# TM1628.net
KiCad netlist of a schematic drawn in Altium Designer
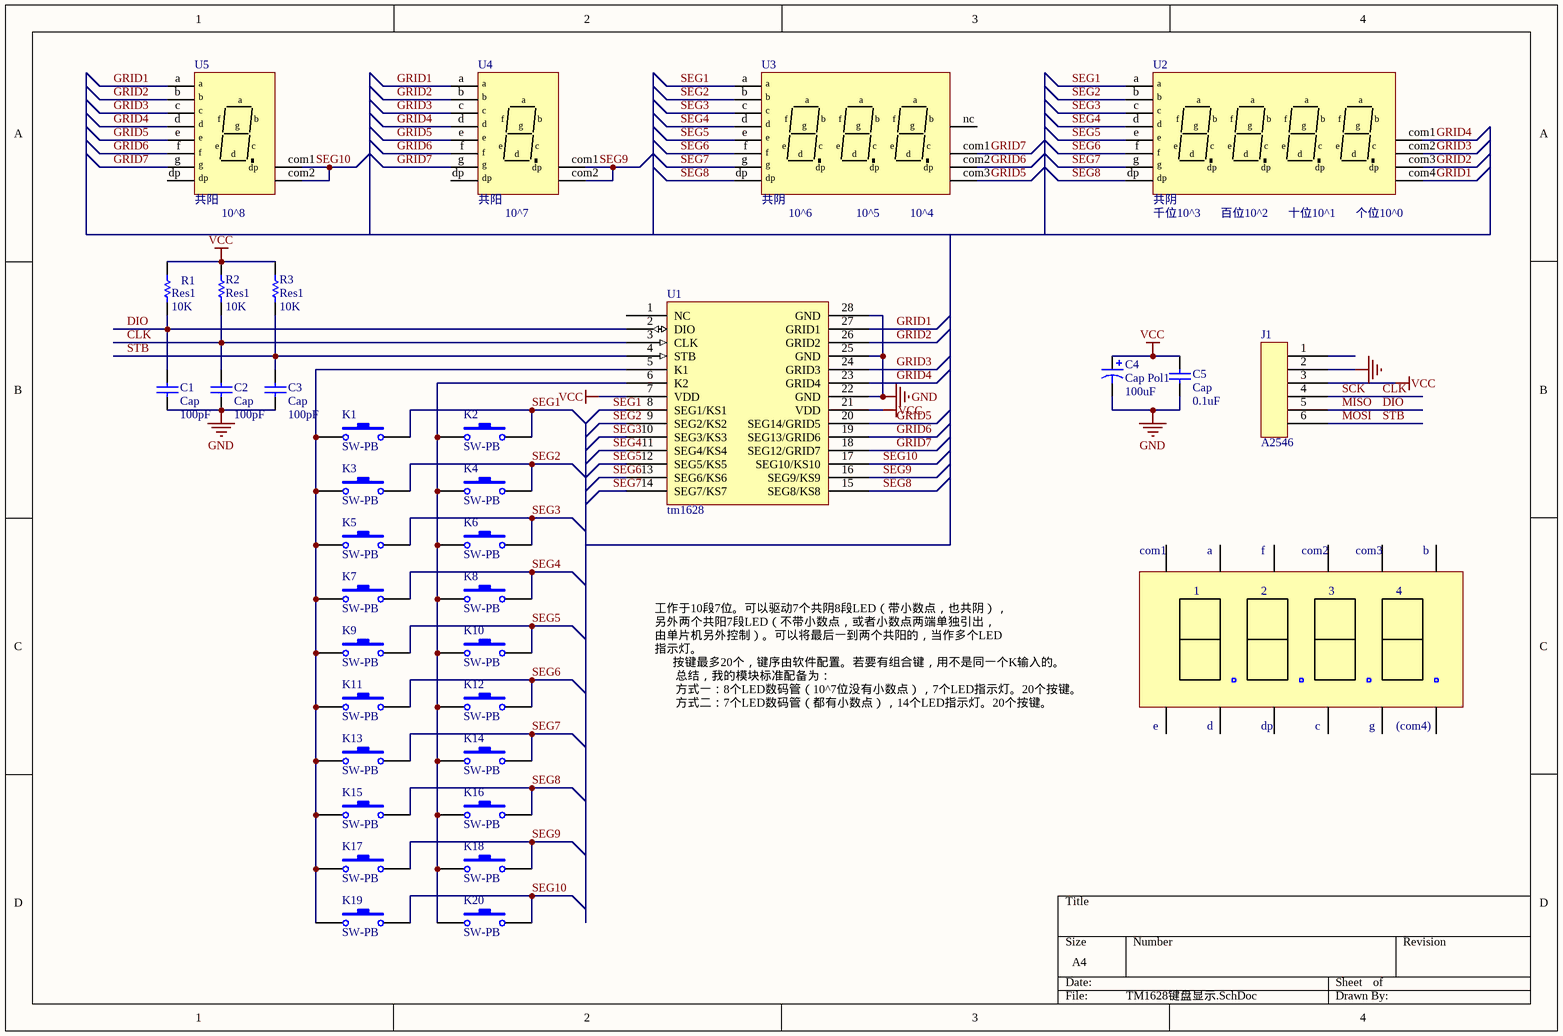
[diagram p0: TM1628键盘显示.SchDoc]

(export (version "E")
  (design (tool "Eeschema 10.0.6"))
  (components
    (comp (ref "C1")
      (value "Cap")
      (footprint "CAPC2512N")
      (description "Capacitor")
      (fields (field (name "ALTIUM_VALUE") "100pF") (field (name "PUBLISHER") "Altium Limited"))
      (libsource (lib "Miscellaneous Devices") (part "Cap"))
    )
    (comp (ref "C2")
      (value "Cap")
      (footprint "CAPC2512N")
      (description "Capacitor")
      (fields (field (name "ALTIUM_VALUE") "100pF") (field (name "PUBLISHER") "Altium Limited"))
      (libsource (lib "Miscellaneous Devices") (part "Cap"))
    )
    (comp (ref "C3")
      (value "Cap")
      (footprint "CAPC2512N")
      (description "Capacitor")
      (fields (field (name "ALTIUM_VALUE") "100pF") (field (name "PUBLISHER") "Altium Limited"))
      (libsource (lib "Miscellaneous Devices") (part "Cap"))
    )
    (comp (ref "C4")
      (value "Cap Pol1")
      (footprint "RB.15/.3")
      (description "Polarized Capacitor (Radial)")
      (fields (field (name "ALTIUM_VALUE") "100uF") (field (name "PUBLISHER") "Altium Limited"))
      (libsource (lib "Miscellaneous Devices") (part "Cap Pol1"))
    )
    (comp (ref "C5")
      (value "Cap")
      (footprint "CAPC2512N")
      (description "Capacitor")
      (fields (field (name "ALTIUM_VALUE") "0.1uF") (field (name "PUBLISHER") "Altium Limited"))
      (libsource (lib "Miscellaneous Devices") (part "Cap"))
    )
    (comp (ref "J1") (value "A2546") (footprint "HDR1X6") (libsource (lib "*") (part "6PIN")))
    (comp (ref "K1")
      (value "SW-PB")
      (footprint "SW-PB")
      (description "Switch")
      (fields (field (name "PUBLISHER") "Altium Limited"))
      (libsource (lib "Miscellaneous Devices") (part "SW-PB"))
    )
    (comp (ref "K2")
      (value "SW-PB")
      (footprint "SW-PB")
      (description "Switch")
      (fields (field (name "PUBLISHER") "Altium Limited"))
      (libsource (lib "Miscellaneous Devices") (part "SW-PB"))
    )
    (comp (ref "K3")
      (value "SW-PB")
      (footprint "SW-PB")
      (description "Switch")
      (fields (field (name "PUBLISHER") "Altium Limited"))
      (libsource (lib "Miscellaneous Devices") (part "SW-PB"))
    )
    (comp (ref "K4")
      (value "SW-PB")
      (footprint "SW-PB")
      (description "Switch")
      (fields (field (name "PUBLISHER") "Altium Limited"))
      (libsource (lib "Miscellaneous Devices") (part "SW-PB"))
    )
    (comp (ref "K5")
      (value "SW-PB")
      (footprint "SW-PB")
      (description "Switch")
      (fields (field (name "PUBLISHER") "Altium Limited"))
      (libsource (lib "Miscellaneous Devices") (part "SW-PB"))
    )
    (comp (ref "K6")
      (value "SW-PB")
      (footprint "SW-PB")
      (description "Switch")
      (fields (field (name "PUBLISHER") "Altium Limited"))
      (libsource (lib "Miscellaneous Devices") (part "SW-PB"))
    )
    (comp (ref "K7")
      (value "SW-PB")
      (footprint "SW-PB")
      (description "Switch")
      (fields (field (name "PUBLISHER") "Altium Limited"))
      (libsource (lib "Miscellaneous Devices") (part "SW-PB"))
    )
    (comp (ref "K8")
      (value "SW-PB")
      (footprint "SW-PB")
      (description "Switch")
      (fields (field (name "PUBLISHER") "Altium Limited"))
      (libsource (lib "Miscellaneous Devices") (part "SW-PB"))
    )
    (comp (ref "K9")
      (value "SW-PB")
      (footprint "SW-PB")
      (description "Switch")
      (fields (field (name "PUBLISHER") "Altium Limited"))
      (libsource (lib "Miscellaneous Devices") (part "SW-PB"))
    )
    (comp (ref "K10")
      (value "SW-PB")
      (footprint "SW-PB")
      (description "Switch")
      (fields (field (name "PUBLISHER") "Altium Limited"))
      (libsource (lib "Miscellaneous Devices") (part "SW-PB"))
    )
    (comp (ref "K11")
      (value "SW-PB")
      (footprint "SW-PB")
      (description "Switch")
      (fields (field (name "PUBLISHER") "Altium Limited"))
      (libsource (lib "Miscellaneous Devices") (part "SW-PB"))
    )
    (comp (ref "K12")
      (value "SW-PB")
      (footprint "SW-PB")
      (description "Switch")
      (fields (field (name "PUBLISHER") "Altium Limited"))
      (libsource (lib "Miscellaneous Devices") (part "SW-PB"))
    )
    (comp (ref "K13")
      (value "SW-PB")
      (footprint "SW-PB")
      (description "Switch")
      (fields (field (name "PUBLISHER") "Altium Limited"))
      (libsource (lib "Miscellaneous Devices") (part "SW-PB"))
    )
    (comp (ref "K14")
      (value "SW-PB")
      (footprint "SW-PB")
      (description "Switch")
      (fields (field (name "PUBLISHER") "Altium Limited"))
      (libsource (lib "Miscellaneous Devices") (part "SW-PB"))
    )
    (comp (ref "K15")
      (value "SW-PB")
      (footprint "SW-PB")
      (description "Switch")
      (fields (field (name "PUBLISHER") "Altium Limited"))
      (libsource (lib "Miscellaneous Devices") (part "SW-PB"))
    )
    (comp (ref "K16")
      (value "SW-PB")
      (footprint "SW-PB")
      (description "Switch")
      (fields (field (name "PUBLISHER") "Altium Limited"))
      (libsource (lib "Miscellaneous Devices") (part "SW-PB"))
    )
    (comp (ref "K17")
      (value "SW-PB")
      (footprint "SW-PB")
      (description "Switch")
      (fields (field (name "PUBLISHER") "Altium Limited"))
      (libsource (lib "Miscellaneous Devices") (part "SW-PB"))
    )
    (comp (ref "K18")
      (value "SW-PB")
      (footprint "SW-PB")
      (description "Switch")
      (fields (field (name "PUBLISHER") "Altium Limited"))
      (libsource (lib "Miscellaneous Devices") (part "SW-PB"))
    )
    (comp (ref "K19")
      (value "SW-PB")
      (footprint "SW-PB")
      (description "Switch")
      (fields (field (name "PUBLISHER") "Altium Limited"))
      (libsource (lib "Miscellaneous Devices") (part "SW-PB"))
    )
    (comp (ref "K20")
      (value "SW-PB")
      (footprint "SW-PB")
      (description "Switch")
      (fields (field (name "PUBLISHER") "Altium Limited"))
      (libsource (lib "Miscellaneous Devices") (part "SW-PB"))
    )
    (comp (ref "R1")
      (value "Res1")
      (footprint "RESC3216N")
      (description "Resistor")
      (fields (field (name "ALTIUM_VALUE") "10K") (field (name "PUBLISHER") "Altium Limited"))
      (libsource (lib "Miscellaneous Devices") (part "Res1"))
    )
    (comp (ref "R2")
      (value "Res1")
      (footprint "RESC3216N")
      (description "Resistor")
      (fields (field (name "ALTIUM_VALUE") "10K") (field (name "PUBLISHER") "Altium Limited"))
      (libsource (lib "Miscellaneous Devices") (part "Res1"))
    )
    (comp (ref "R3")
      (value "Res1")
      (footprint "RESC3216N")
      (description "Resistor")
      (fields (field (name "ALTIUM_VALUE") "10K") (field (name "PUBLISHER") "Altium Limited"))
      (libsource (lib "Miscellaneous Devices") (part "Res1"))
    )
    (comp (ref "U1") (value "tm1628") (footprint "SOP28") (libsource (lib "CHANG15_SCH") (part "tm1628")))
    (comp (ref "U2")
      (value "共阴")
      (footprint "SR420561")
      (description "CP-SR420561K")
      (libsource (lib "photounit") (part "SR420561K"))
    )
    (comp (ref "U3")
      (value "共阴")
      (footprint "SP410561")
      (description "CP-SP410561K")
      (libsource (lib "photounit") (part "SP410561K"))
    )
    (comp (ref "U4")
      (value "共阳")
      (footprint "SN450561")
      (description "CP-SN450561K")
      (libsource (lib "photounit") (part "SN450561K"))
    )
    (comp (ref "U5")
      (value "共阳")
      (footprint "SN450561")
      (description "CP-SN450561K")
      (libsource (lib "photounit") (part "SN450561K"))
    )
  )
  (nets
    (net (code "1") (name "/CLK") (class "Default")
      (node (ref "C2") (pin "2") (pinfunction "2_2") (pintype "passive"))
      (node (ref "J1") (pin "4") (pintype "passive"))
      (node (ref "R2") (pin "1") (pinfunction "1_1") (pintype "passive"))
      (node (ref "U1") (pin "3") (pinfunction "CLK_3") (pintype "input"))
    )
    (net (code "2") (name "/DIO") (class "Default")
      (node (ref "C1") (pin "2") (pinfunction "2_2") (pintype "passive"))
      (node (ref "J1") (pin "5") (pintype "passive"))
      (node (ref "R1") (pin "1") (pinfunction "1_1") (pintype "passive"))
      (node (ref "U1") (pin "2") (pinfunction "DIO_2") (pintype "bidirectional"))
    )
    (net (code "3") (name "/GRID1") (class "Default")
      (node (ref "U1") (pin "27") (pinfunction "GRID1_27") (pintype "passive"))
      (node (ref "U2") (pin "com4") (pinfunction "com4_com4") (pintype "passive"))
      (node (ref "U4") (pin "a") (pinfunction "a_a") (pintype "passive"))
      (node (ref "U5") (pin "a") (pinfunction "a_a") (pintype "passive"))
    )
    (net (code "4") (name "/GRID2") (class "Default")
      (node (ref "U1") (pin "26") (pinfunction "GRID2_26") (pintype "power_in"))
      (node (ref "U2") (pin "com3") (pinfunction "com3_com3") (pintype "passive"))
      (node (ref "U4") (pin "b") (pinfunction "b_b") (pintype "passive"))
      (node (ref "U5") (pin "b") (pinfunction "b_b") (pintype "passive"))
    )
    (net (code "5") (name "/GRID3") (class "Default")
      (node (ref "U1") (pin "24") (pinfunction "GRID3_24") (pintype "passive"))
      (node (ref "U2") (pin "com2") (pinfunction "com2_com2") (pintype "passive"))
      (node (ref "U4") (pin "c") (pinfunction "c_c") (pintype "passive"))
      (node (ref "U5") (pin "c") (pinfunction "c_c") (pintype "passive"))
    )
    (net (code "6") (name "/GRID4") (class "Default")
      (node (ref "U1") (pin "23") (pinfunction "GRID4_23") (pintype "passive"))
      (node (ref "U2") (pin "com1") (pinfunction "com1_com1") (pintype "passive"))
      (node (ref "U4") (pin "d") (pinfunction "d_d") (pintype "passive"))
      (node (ref "U5") (pin "d") (pinfunction "d_d") (pintype "passive"))
    )
    (net (code "7") (name "/GRID5") (class "Default")
      (node (ref "U1") (pin "20") (pinfunction "SEG14/GRID5_20") (pintype "passive"))
      (node (ref "U3") (pin "com3") (pinfunction "com3_com3") (pintype "passive"))
      (node (ref "U4") (pin "e") (pinfunction "e_e") (pintype "passive"))
      (node (ref "U5") (pin "e") (pinfunction "e_e") (pintype "passive"))
    )
    (net (code "8") (name "/GRID6") (class "Default")
      (node (ref "U1") (pin "19") (pinfunction "SEG13/GRID6_19") (pintype "passive"))
      (node (ref "U3") (pin "com2") (pinfunction "com2_com2") (pintype "passive"))
      (node (ref "U4") (pin "f") (pinfunction "f_f") (pintype "passive"))
      (node (ref "U5") (pin "f") (pinfunction "f_f") (pintype "passive"))
    )
    (net (code "9") (name "/GRID7") (class "Default")
      (node (ref "U1") (pin "18") (pinfunction "SEG12/GRID7_18") (pintype "passive"))
      (node (ref "U3") (pin "com1") (pinfunction "com1_com1") (pintype "passive"))
      (node (ref "U4") (pin "g") (pinfunction "g_g") (pintype "passive"))
      (node (ref "U5") (pin "g") (pinfunction "g_g") (pintype "passive"))
    )
    (net (code "10") (name "/MOSI") (class "Default")
      (node (ref "C3") (pin "2") (pinfunction "2_2") (pintype "passive"))
      (node (ref "J1") (pin "6") (pintype "passive"))
      (node (ref "R3") (pin "1") (pinfunction "1_1") (pintype "passive"))
      (node (ref "U1") (pin "4") (pinfunction "STB_4") (pintype "input"))
    )
    (net (code "11") (name "/SEG1") (class "Default")
      (node (ref "K1") (pin "2") (pinfunction "2_2") (pintype "passive"))
      (node (ref "K2") (pin "2") (pinfunction "2_2") (pintype "passive"))
      (node (ref "U1") (pin "8") (pinfunction "SEG1/KS1_8") (pintype "passive"))
      (node (ref "U2") (pin "a") (pinfunction "a_a") (pintype "passive"))
      (node (ref "U3") (pin "a") (pinfunction "a_a") (pintype "passive"))
    )
    (net (code "12") (name "/SEG2") (class "Default")
      (node (ref "K3") (pin "2") (pinfunction "2_2") (pintype "passive"))
      (node (ref "K4") (pin "2") (pinfunction "2_2") (pintype "passive"))
      (node (ref "U1") (pin "9") (pinfunction "SEG2/KS2_9") (pintype "passive"))
      (node (ref "U2") (pin "b") (pinfunction "b_b") (pintype "passive"))
      (node (ref "U3") (pin "b") (pinfunction "b_b") (pintype "passive"))
    )
    (net (code "13") (name "/SEG3") (class "Default")
      (node (ref "K5") (pin "2") (pinfunction "2_2") (pintype "passive"))
      (node (ref "K6") (pin "2") (pinfunction "2_2") (pintype "passive"))
      (node (ref "U1") (pin "10") (pinfunction "SEG3/KS3_10") (pintype "passive"))
      (node (ref "U2") (pin "c") (pinfunction "c_c") (pintype "passive"))
      (node (ref "U3") (pin "c") (pinfunction "c_c") (pintype "passive"))
    )
    (net (code "14") (name "/SEG4") (class "Default")
      (node (ref "K7") (pin "2") (pinfunction "2_2") (pintype "passive"))
      (node (ref "K8") (pin "2") (pinfunction "2_2") (pintype "passive"))
      (node (ref "U1") (pin "11") (pinfunction "SEG4/KS4_11") (pintype "passive"))
      (node (ref "U2") (pin "d") (pinfunction "d_d") (pintype "passive"))
      (node (ref "U3") (pin "d") (pinfunction "d_d") (pintype "passive"))
    )
    (net (code "15") (name "/SEG5") (class "Default")
      (node (ref "K10") (pin "2") (pinfunction "2_2") (pintype "passive"))
      (node (ref "K9") (pin "2") (pinfunction "2_2") (pintype "passive"))
      (node (ref "U1") (pin "12") (pinfunction "SEG5/KS5_12") (pintype "passive"))
      (node (ref "U2") (pin "e") (pinfunction "e_e") (pintype "passive"))
      (node (ref "U3") (pin "e") (pinfunction "e_e") (pintype "passive"))
    )
    (net (code "16") (name "/SEG6") (class "Default")
      (node (ref "K11") (pin "2") (pinfunction "2_2") (pintype "passive"))
      (node (ref "K12") (pin "2") (pinfunction "2_2") (pintype "passive"))
      (node (ref "U1") (pin "13") (pinfunction "SEG6/KS6_13") (pintype "passive"))
      (node (ref "U2") (pin "f") (pinfunction "f_f") (pintype "passive"))
      (node (ref "U3") (pin "f") (pinfunction "f_f") (pintype "passive"))
    )
    (net (code "17") (name "/SEG7") (class "Default")
      (node (ref "K13") (pin "2") (pinfunction "2_2") (pintype "passive"))
      (node (ref "K14") (pin "2") (pinfunction "2_2") (pintype "passive"))
      (node (ref "U1") (pin "14") (pinfunction "SEG7/KS7_14") (pintype "passive"))
      (node (ref "U2") (pin "g") (pinfunction "g_g") (pintype "passive"))
      (node (ref "U3") (pin "g") (pinfunction "g_g") (pintype "passive"))
    )
    (net (code "18") (name "/SEG8") (class "Default")
      (node (ref "K15") (pin "2") (pinfunction "2_2") (pintype "passive"))
      (node (ref "K16") (pin "2") (pinfunction "2_2") (pintype "passive"))
      (node (ref "U1") (pin "15") (pinfunction "SEG8/KS8_15") (pintype "passive"))
      (node (ref "U2") (pin "dp") (pinfunction "dp_dp") (pintype "passive"))
      (node (ref "U3") (pin "dp") (pinfunction "dp_dp") (pintype "passive"))
    )
    (net (code "19") (name "/SEG9") (class "Default")
      (node (ref "K17") (pin "2") (pinfunction "2_2") (pintype "passive"))
      (node (ref "K18") (pin "2") (pinfunction "2_2") (pintype "passive"))
      (node (ref "U1") (pin "16") (pinfunction "SEG9/KS9_16") (pintype "passive"))
      (node (ref "U4") (pin "com1") (pinfunction "com1_com1") (pintype "passive"))
      (node (ref "U4") (pin "com2") (pinfunction "com2_com2") (pintype "passive"))
    )
    (net (code "20") (name "/SEG10") (class "Default")
      (node (ref "K19") (pin "2") (pinfunction "2_2") (pintype "passive"))
      (node (ref "K20") (pin "2") (pinfunction "2_2") (pintype "passive"))
      (node (ref "U1") (pin "17") (pinfunction "SEG10/KS10_17") (pintype "passive"))
      (node (ref "U5") (pin "com1") (pinfunction "com1_com1") (pintype "passive"))
      (node (ref "U5") (pin "com2") (pinfunction "com2_com2") (pintype "passive"))
    )
    (net (code "21") (name "GND") (class "Default")
      (node (ref "C1") (pin "1") (pinfunction "1_1") (pintype "passive"))
      (node (ref "C2") (pin "1") (pinfunction "1_1") (pintype "passive"))
      (node (ref "C3") (pin "1") (pinfunction "1_1") (pintype "passive"))
      (node (ref "C4") (pin "2") (pinfunction "2_2") (pintype "passive"))
      (node (ref "C5") (pin "1") (pinfunction "1_1") (pintype "passive"))
      (node (ref "J1") (pin "2") (pintype "passive"))
      (node (ref "U1") (pin "22") (pinfunction "GND_22") (pintype "power_in"))
      (node (ref "U1") (pin "25") (pinfunction "GND_25") (pintype "power_in"))
      (node (ref "U1") (pin "28") (pinfunction "GND_28") (pintype "power_in"))
    )
    (net (code "22") (name "Net-(U1-K1)") (class "Default")
      (node (ref "K1") (pin "1") (pinfunction "1_1") (pintype "passive"))
      (node (ref "K11") (pin "1") (pinfunction "1_1") (pintype "passive"))
      (node (ref "K13") (pin "1") (pinfunction "1_1") (pintype "passive"))
      (node (ref "K15") (pin "1") (pinfunction "1_1") (pintype "passive"))
      (node (ref "K17") (pin "1") (pinfunction "1_1") (pintype "passive"))
      (node (ref "K19") (pin "1") (pinfunction "1_1") (pintype "passive"))
      (node (ref "K3") (pin "1") (pinfunction "1_1") (pintype "passive"))
      (node (ref "K5") (pin "1") (pinfunction "1_1") (pintype "passive"))
      (node (ref "K7") (pin "1") (pinfunction "1_1") (pintype "passive"))
      (node (ref "K9") (pin "1") (pinfunction "1_1") (pintype "passive"))
      (node (ref "U1") (pin "5") (pinfunction "K1_5") (pintype "passive"))
    )
    (net (code "23") (name "Net-(U1-K2)") (class "Default")
      (node (ref "K10") (pin "1") (pinfunction "1_1") (pintype "passive"))
      (node (ref "K12") (pin "1") (pinfunction "1_1") (pintype "passive"))
      (node (ref "K14") (pin "1") (pinfunction "1_1") (pintype "passive"))
      (node (ref "K16") (pin "1") (pinfunction "1_1") (pintype "passive"))
      (node (ref "K18") (pin "1") (pinfunction "1_1") (pintype "passive"))
      (node (ref "K2") (pin "1") (pinfunction "1_1") (pintype "passive"))
      (node (ref "K20") (pin "1") (pinfunction "1_1") (pintype "passive"))
      (node (ref "K4") (pin "1") (pinfunction "1_1") (pintype "passive"))
      (node (ref "K6") (pin "1") (pinfunction "1_1") (pintype "passive"))
      (node (ref "K8") (pin "1") (pinfunction "1_1") (pintype "passive"))
      (node (ref "U1") (pin "6") (pinfunction "K2_6") (pintype "passive"))
    )
    (net (code "24") (name "VCC") (class "Default")
      (node (ref "C4") (pin "1") (pinfunction "1_1") (pintype "passive"))
      (node (ref "C5") (pin "2") (pinfunction "2_2") (pintype "passive"))
      (node (ref "J1") (pin "3") (pintype "passive"))
      (node (ref "R1") (pin "2") (pinfunction "2_2") (pintype "passive"))
      (node (ref "R2") (pin "2") (pinfunction "2_2") (pintype "passive"))
      (node (ref "R3") (pin "2") (pinfunction "2_2") (pintype "passive"))
      (node (ref "U1") (pin "21") (pinfunction "VDD_21") (pintype "power_in"))
      (node (ref "U1") (pin "7") (pinfunction "VDD_7") (pintype "power_in"))
    )
    (net (code "25") (name "unconnected-(J1-Pad1)") (class "Default")
      (node (ref "J1") (pin "1") (pintype "passive"))
    )
    (net (code "26") (name "unconnected-(U1-NC-Pad1)") (class "Default")
      (node (ref "U1") (pin "1") (pinfunction "NC_1") (pintype "tri_state"))
    )
    (net (code "27") (name "unconnected-(U3-Padnc)") (class "Default")
      (node (ref "U3") (pin "nc") (pinfunction "nc_nc") (pintype "passive"))
    )
    (net (code "28") (name "unconnected-(U4-Paddp)") (class "Default")
      (node (ref "U4") (pin "dp") (pinfunction "dp_dp") (pintype "passive"))
    )
    (net (code "29") (name "unconnected-(U5-Paddp)") (class "Default")
      (node (ref "U5") (pin "dp") (pinfunction "dp_dp") (pintype "passive"))
    )
  )
)
